# rev1.net
KiCad netlist of a schematic drawn in EAGLE
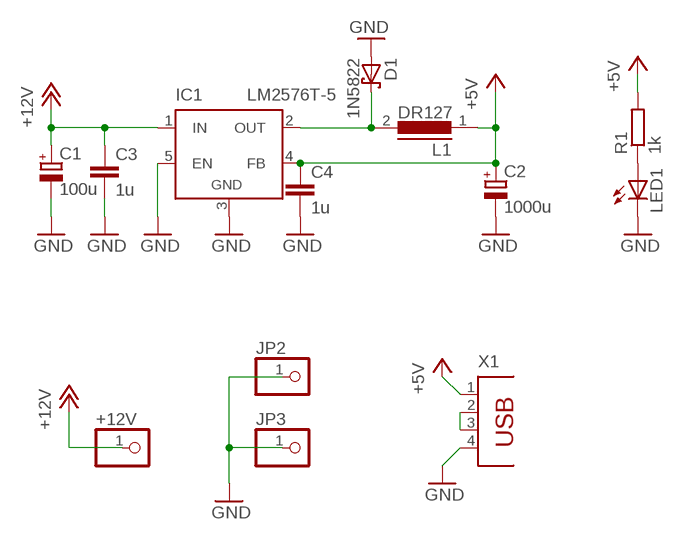
[diagram p0: schematic, sheet 1]

(export (version "E")
  (design (tool "Eeschema 10.0.6"))
  (components
    (comp (ref "+12V")
      (value "PINHD-1X1")
      (footprint "eagle-import:1X01")
      (libsource (lib "eagle-import") (part "PINHD-1X1"))
    )
    (comp (ref "C1")
      (value "100u")
      (footprint "eagle-import:TT2D6L")
      (libsource (lib "eagle-import") (part "CPOL-EUTT2D6L"))
    )
    (comp (ref "C2")
      (value "1000u")
      (footprint "eagle-import:TT5D9L")
      (libsource (lib "eagle-import") (part "CPOL-EUTT5D9L"))
    )
    (comp (ref "C3")
      (value "1u")
      (footprint "eagle-import:C0805K")
      (libsource (lib "eagle-import") (part "C-EUC0805K"))
    )
    (comp (ref "C4")
      (value "1u")
      (footprint "eagle-import:C0805K")
      (libsource (lib "eagle-import") (part "C-EUC0805K"))
    )
    (comp (ref "D1")
      (value "1N5822")
      (footprint "eagle-import:DO201_5")
      (libsource (lib "eagle-import") (part "1N5822"))
    )
    (comp (ref "IC1")
      (value "LM2576T-5")
      (footprint "eagle-import:TO220-51")
      (libsource (lib "eagle-import") (part "LM2596TV"))
    )
    (comp (ref "JP2")
      (value "PINHD-1X1")
      (footprint "eagle-import:1X01")
      (libsource (lib "eagle-import") (part "PINHD-1X1"))
    )
    (comp (ref "JP3")
      (value "PINHD-1X1")
      (footprint "eagle-import:1X01")
      (libsource (lib "eagle-import") (part "PINHD-1X1"))
    )
    (comp (ref "L1")
      (value "DR127")
      (footprint "eagle-import:DR127")
      (libsource (lib "eagle-import") (part "DR127"))
    )
    (comp (ref "LED1")
      (value "LED3MM")
      (footprint "eagle-import:LED3MM")
      (libsource (lib "eagle-import") (part "LED3MM"))
    )
    (comp (ref "R1")
      (value "1k")
      (footprint "eagle-import:R0805")
      (libsource (lib "eagle-import") (part "R-EU_R0805"))
    )
    (comp (ref "X1")
      (value "PN87520")
      (footprint "eagle-import:PN87520")
      (libsource (lib "eagle-import") (part "PN87520"))
    )
  )
  (nets
    (net (code "1") (name "+5V") (class "Default")
      (node (ref "C2") (pin "+") (pinfunction "+_+") (pintype "passive"))
      (node (ref "C4") (pin "1") (pinfunction "1_1") (pintype "passive"))
      (node (ref "IC1") (pin "4") (pinfunction "FB_4") (pintype "input"))
      (node (ref "L1") (pin "1") (pinfunction "1_1") (pintype "passive"))
      (node (ref "R1") (pin "2") (pinfunction "2_2") (pintype "passive"))
      (node (ref "X1") (pin "1") (pinfunction "1_1") (pintype "passive"))
    )
    (net (code "2") (name "+12V") (class "Default")
      (node (ref "+12V") (pin "1") (pinfunction "1_1") (pintype "passive"))
      (node (ref "C1") (pin "+") (pinfunction "+_+") (pintype "passive"))
      (node (ref "C3") (pin "1") (pinfunction "1_1") (pintype "passive"))
      (node (ref "IC1") (pin "1") (pinfunction "IN_1") (pintype "input"))
    )
    (net (code "3") (name "GND") (class "Default")
      (node (ref "C1") (pin "-") (pinfunction "-_-") (pintype "passive"))
      (node (ref "C2") (pin "-") (pinfunction "-_-") (pintype "passive"))
      (node (ref "C3") (pin "2") (pinfunction "2_2") (pintype "passive"))
      (node (ref "C4") (pin "2") (pinfunction "2_2") (pintype "passive"))
      (node (ref "D1") (pin "P$2") (pinfunction "A_P$2") (pintype "passive"))
      (node (ref "IC1") (pin "3") (pinfunction "GND_3") (pintype "power_in"))
      (node (ref "IC1") (pin "5") (pinfunction "EN_5") (pintype "input"))
      (node (ref "JP2") (pin "1") (pinfunction "1_1") (pintype "passive"))
      (node (ref "JP3") (pin "1") (pinfunction "1_1") (pintype "passive"))
      (node (ref "LED1") (pin "K") (pinfunction "C_K") (pintype "passive"))
      (node (ref "X1") (pin "4") (pinfunction "4_4") (pintype "passive"))
    )
    (net (code "4") (name "Net-(D1-C)") (class "Default")
      (node (ref "D1") (pin "P$1") (pinfunction "C_P$1") (pintype "passive"))
      (node (ref "IC1") (pin "2") (pinfunction "OUT_2") (pintype "output"))
      (node (ref "L1") (pin "2") (pinfunction "2_2") (pintype "passive"))
    )
    (net (code "5") (name "Net-(LED1-PadA)") (class "Default")
      (node (ref "LED1") (pin "A") (pinfunction "A_A") (pintype "passive"))
      (node (ref "R1") (pin "1") (pinfunction "1_1") (pintype "passive"))
    )
    (net (code "6") (name "Net-(X1-Pad2)") (class "Default")
      (node (ref "X1") (pin "2") (pinfunction "2_2") (pintype "passive"))
      (node (ref "X1") (pin "3") (pinfunction "3_3") (pintype "passive"))
    )
  )
)
